# 04A-005.net
KiCad netlist of a schematic drawn in EAGLE
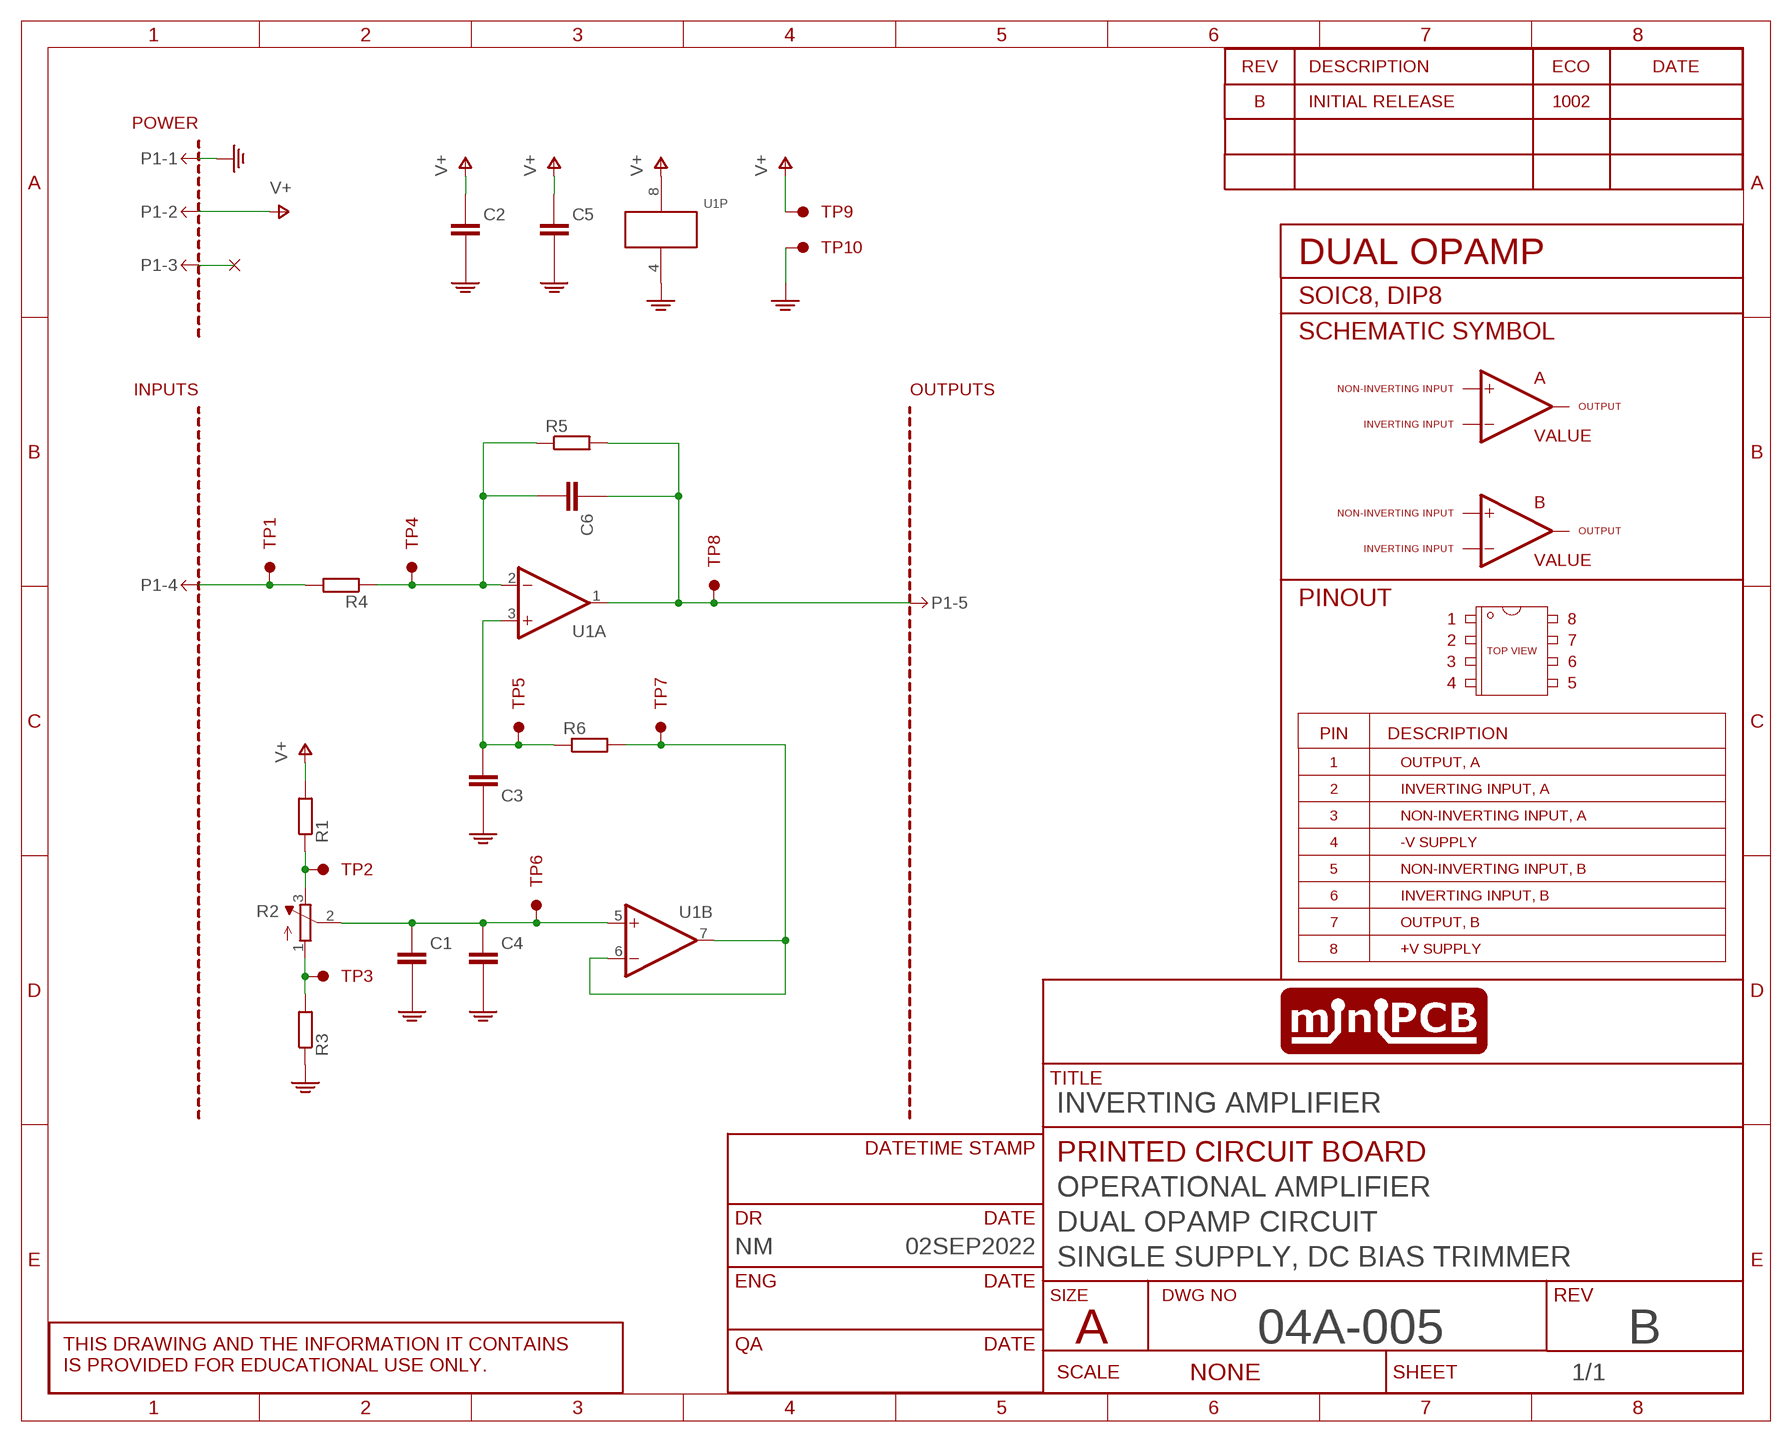
[diagram p0: schematic, sheet 1]

(export (version "E")
  (design (tool "Eeschema 10.0.6"))
  (components
    (comp (ref "C1")
      (value "CAPACITORTHD")
      (footprint "eagle-import:C050-024X044")
      (libsource (lib "eagle-import") (part "CAPACITORTHD"))
    )
    (comp (ref "C2")
      (value "CAPACITORTHD")
      (footprint "eagle-import:C050-024X044")
      (libsource (lib "eagle-import") (part "CAPACITORTHD"))
    )
    (comp (ref "C3")
      (value "CAPACITORTHD")
      (footprint "eagle-import:C050-024X044")
      (libsource (lib "eagle-import") (part "CAPACITORTHD"))
    )
    (comp (ref "C4")
      (value "CAPACITORTHD")
      (footprint "eagle-import:C050-024X044")
      (libsource (lib "eagle-import") (part "CAPACITORTHD"))
    )
    (comp (ref "C5")
      (value "CAPACITORTHD")
      (footprint "eagle-import:C050-024X044")
      (libsource (lib "eagle-import") (part "CAPACITORTHD"))
    )
    (comp (ref "C6")
      (value "CAPACITORTHD")
      (footprint "eagle-import:C050-024X044")
      (libsource (lib "eagle-import") (part "CAPACITORTHD"))
    )
    (comp (ref "P1-")
      (value "MINIPCB_5P50X50")
      (footprint "eagle-import:MINIPCB_5P_50X50MM")
      (fields (field (name "PART_NUMBER") "X04A-005-B") (field (name "REVISION") "B"))
      (libsource (lib "eagle-import") (part "MINIPCB_5P50X50"))
    )
    (comp (ref "R1")
      (value "RESISTOR10MM")
      (footprint "eagle-import:0207_10")
      (libsource (lib "eagle-import") (part "RESISTOR10MM"))
    )
    (comp (ref "R2")
      (value "TRIMPOT0.100THD")
      (footprint "eagle-import:TRIM_0100")
      (libsource (lib "eagle-import") (part "TRIMPOT0.100THD"))
    )
    (comp (ref "R3")
      (value "RESISTOR10MM")
      (footprint "eagle-import:0207_10")
      (libsource (lib "eagle-import") (part "RESISTOR10MM"))
    )
    (comp (ref "R4")
      (value "RESISTOR10MM")
      (footprint "eagle-import:0207_10")
      (libsource (lib "eagle-import") (part "RESISTOR10MM"))
    )
    (comp (ref "R5")
      (value "RESISTOR10MM")
      (footprint "eagle-import:0207_10")
      (libsource (lib "eagle-import") (part "RESISTOR10MM"))
    )
    (comp (ref "R6")
      (value "RESISTOR10MM")
      (footprint "eagle-import:0207_10")
      (libsource (lib "eagle-import") (part "RESISTOR10MM"))
    )
    (comp (ref "TP1")
      (value "TESTPOINTKE5000-SMTEXT")
      (footprint "eagle-import:PINS_1_TESTPOINT_KE5000_NOTEXT")
      (libsource (lib "eagle-import") (part "TESTPOINTKE5000-SMTEXT"))
    )
    (comp (ref "TP2")
      (value "TESTPOINTKE5000-SMTEXT")
      (footprint "eagle-import:PINS_1_TESTPOINT_KE5000_NOTEXT")
      (libsource (lib "eagle-import") (part "TESTPOINTKE5000-SMTEXT"))
    )
    (comp (ref "TP3")
      (value "TESTPOINTKE5000-SMTEXT")
      (footprint "eagle-import:PINS_1_TESTPOINT_KE5000_NOTEXT")
      (libsource (lib "eagle-import") (part "TESTPOINTKE5000-SMTEXT"))
    )
    (comp (ref "TP4")
      (value "TESTPOINTKE5000-SMTEXT")
      (footprint "eagle-import:PINS_1_TESTPOINT_KE5000_NOTEXT")
      (libsource (lib "eagle-import") (part "TESTPOINTKE5000-SMTEXT"))
    )
    (comp (ref "TP5")
      (value "TESTPOINTKE5000-SMTEXT")
      (footprint "eagle-import:PINS_1_TESTPOINT_KE5000_NOTEXT")
      (libsource (lib "eagle-import") (part "TESTPOINTKE5000-SMTEXT"))
    )
    (comp (ref "TP6")
      (value "TESTPOINTKE5000-SMTEXT")
      (footprint "eagle-import:PINS_1_TESTPOINT_KE5000_NOTEXT")
      (libsource (lib "eagle-import") (part "TESTPOINTKE5000-SMTEXT"))
    )
    (comp (ref "TP7")
      (value "TESTPOINTKE5000-SMTEXT")
      (footprint "eagle-import:PINS_1_TESTPOINT_KE5000_NOTEXT")
      (libsource (lib "eagle-import") (part "TESTPOINTKE5000-SMTEXT"))
    )
    (comp (ref "TP8")
      (value "TESTPOINTKE5000-SMTEXT")
      (footprint "eagle-import:PINS_1_TESTPOINT_KE5000_NOTEXT")
      (libsource (lib "eagle-import") (part "TESTPOINTKE5000-SMTEXT"))
    )
    (comp (ref "TP9")
      (value "TESTPOINTKE5000-SMTEXT")
      (footprint "eagle-import:PINS_1_TESTPOINT_KE5000_NOTEXT")
      (libsource (lib "eagle-import") (part "TESTPOINTKE5000-SMTEXT"))
    )
    (comp (ref "TP10")
      (value "TESTPOINTKE5000-SMTEXT")
      (footprint "eagle-import:PINS_1_TESTPOINT_KE5000_NOTEXT")
      (libsource (lib "eagle-import") (part "TESTPOINTKE5000-SMTEXT"))
    )
    (comp (ref "U1")
      (value "OPAMP_DUALTHD")
      (footprint "eagle-import:DIL08")
      (libsource (lib "eagle-import") (part "OPAMP_DUALTHD"))
    )
  )
  (nets
    (net (code "1") (name "GND") (class "Default")
      (node (ref "C1") (pin "2") (pinfunction "-_2") (pintype "passive"))
      (node (ref "C2") (pin "2") (pinfunction "-_2") (pintype "passive"))
      (node (ref "C3") (pin "1") (pinfunction "+_1") (pintype "passive"))
      (node (ref "C4") (pin "2") (pinfunction "-_2") (pintype "passive"))
      (node (ref "C5") (pin "2") (pinfunction "-_2") (pintype "passive"))
      (node (ref "P1-") (pin "1") (pinfunction "1_1") (pintype "bidirectional"))
      (node (ref "R3") (pin "1") (pinfunction "1_1") (pintype "passive"))
      (node (ref "TP10") (pin "1") (pinfunction "1_1") (pintype "bidirectional"))
      (node (ref "U1") (pin "4") (pinfunction "V-_4") (pintype "power_in"))
    )
    (net (code "2") (name "Net-(C1-+)") (class "Default")
      (node (ref "C1") (pin "1") (pinfunction "+_1") (pintype "passive"))
      (node (ref "C4") (pin "1") (pinfunction "+_1") (pintype "passive"))
      (node (ref "R2") (pin "2") (pinfunction "S_2") (pintype "passive"))
      (node (ref "TP6") (pin "1") (pinfunction "1_1") (pintype "bidirectional"))
      (node (ref "U1") (pin "5") (pinfunction "+IN_5") (pintype "input"))
    )
    (net (code "3") (name "Net-(C3--)") (class "Default")
      (node (ref "C3") (pin "2") (pinfunction "-_2") (pintype "passive"))
      (node (ref "R6") (pin "1") (pinfunction "1_1") (pintype "passive"))
      (node (ref "TP5") (pin "1") (pinfunction "1_1") (pintype "bidirectional"))
      (node (ref "U1") (pin "3") (pinfunction "+IN_3") (pintype "input"))
    )
    (net (code "4") (name "Net-(C6-+)") (class "Default")
      (node (ref "C6") (pin "1") (pinfunction "+_1") (pintype "passive"))
      (node (ref "P1-") (pin "5") (pinfunction "1_5") (pintype "bidirectional"))
      (node (ref "R5") (pin "2") (pinfunction "2_2") (pintype "passive"))
      (node (ref "TP8") (pin "1") (pinfunction "1_1") (pintype "bidirectional"))
      (node (ref "U1") (pin "1") (pinfunction "OUT_1") (pintype "output"))
    )
    (net (code "5") (name "Net-(C6--)") (class "Default")
      (node (ref "C6") (pin "2") (pinfunction "-_2") (pintype "passive"))
      (node (ref "R4") (pin "1") (pinfunction "1_1") (pintype "passive"))
      (node (ref "R5") (pin "1") (pinfunction "1_1") (pintype "passive"))
      (node (ref "TP4") (pin "1") (pinfunction "1_1") (pintype "bidirectional"))
      (node (ref "U1") (pin "2") (pinfunction "-IN_2") (pintype "input"))
    )
    (net (code "6") (name "Net-(P1-D-1)") (class "Default")
      (node (ref "P1-") (pin "4") (pinfunction "1_4") (pintype "bidirectional"))
      (node (ref "R4") (pin "2") (pinfunction "2_2") (pintype "passive"))
      (node (ref "TP1") (pin "1") (pinfunction "1_1") (pintype "bidirectional"))
    )
    (net (code "7") (name "Net-(R2-A)") (class "Default")
      (node (ref "R2") (pin "1") (pinfunction "A_1") (pintype "passive"))
      (node (ref "R3") (pin "2") (pinfunction "2_2") (pintype "passive"))
      (node (ref "TP3") (pin "1") (pinfunction "1_1") (pintype "bidirectional"))
    )
    (net (code "8") (name "Net-(R2-E)") (class "Default")
      (node (ref "R1") (pin "1") (pinfunction "1_1") (pintype "passive"))
      (node (ref "R2") (pin "3") (pinfunction "E_3") (pintype "passive"))
      (node (ref "TP2") (pin "1") (pinfunction "1_1") (pintype "bidirectional"))
    )
    (net (code "9") (name "Net-(U1B--IN)") (class "Default")
      (node (ref "R6") (pin "2") (pinfunction "2_2") (pintype "passive"))
      (node (ref "TP7") (pin "1") (pinfunction "1_1") (pintype "bidirectional"))
      (node (ref "U1") (pin "6") (pinfunction "-IN_6") (pintype "input"))
      (node (ref "U1") (pin "7") (pinfunction "OUT_7") (pintype "output"))
    )
    (net (code "10") (name "V+") (class "Default")
      (node (ref "C2") (pin "1") (pinfunction "+_1") (pintype "passive"))
      (node (ref "C5") (pin "1") (pinfunction "+_1") (pintype "passive"))
      (node (ref "P1-") (pin "2") (pinfunction "1_2") (pintype "bidirectional"))
      (node (ref "R1") (pin "2") (pinfunction "2_2") (pintype "passive"))
      (node (ref "TP9") (pin "1") (pinfunction "1_1") (pintype "bidirectional"))
      (node (ref "U1") (pin "8") (pinfunction "V+_8") (pintype "power_in"))
    )
    (net (code "11") (name "unconnected-(P1-C-1-Pad3)") (class "Default")
      (node (ref "P1-") (pin "3") (pinfunction "1_3") (pintype "bidirectional"))
    )
  )
)
